# 01_stm32.net
KiCad netlist of a schematic drawn in Altium Designer
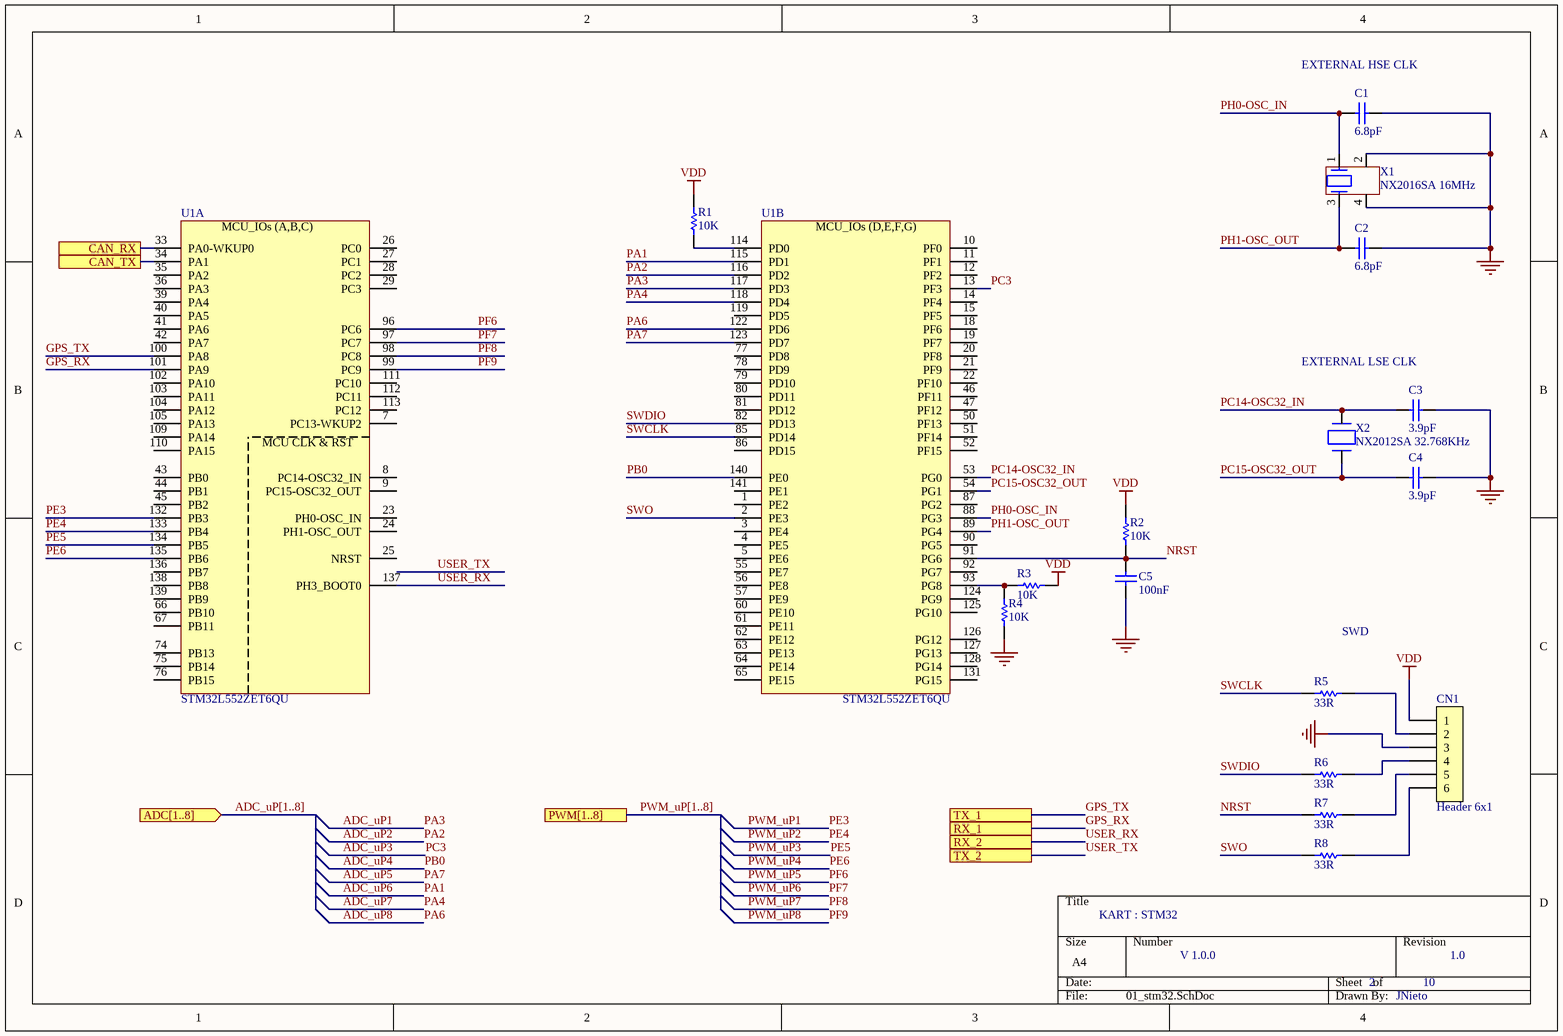
[diagram p0: 01_stm32.SchDoc]

(export (version "E")
  (design (tool "Eeschema 10.0.6"))
  (components
    (comp (ref "C1")
      (value "6.8pF")
      (footprint "C0603")
      (description "Capacitor, MLCC, 6.8pF, 50V, NPO, +-0.25pF, 0402, T=0.5mm")
      (fields
        (field (name "INTERNAL_PART_NUMBER") "MCD-00674")
        (field (name "MANUFACTURER_PART_NUMBER") "CC0402CRNPO9BN6R8")
        (field (name "PROVIDED_BY") "Subcon")
      )
      (libsource (lib "stm32l552_launchpad") (part "MCD-00674"))
    )
    (comp (ref "C2")
      (value "6.8pF")
      (footprint "C0603")
      (description "Capacitor, MLCC, 6.8pF, 50V, NPO, +-0.25pF, 0402, T=0.5mm")
      (fields
        (field (name "INTERNAL_PART_NUMBER") "MCD-00674")
        (field (name "MANUFACTURER_PART_NUMBER") "CC0402CRNPO9BN6R8")
        (field (name "PROVIDED_BY") "Subcon")
      )
      (libsource (lib "stm32l552_launchpad") (part "MCD-00674"))
    )
    (comp (ref "C3")
      (value "3.9pF")
      (footprint "C0603")
      (description "Capacitor, MLCC, 3.9pF, 50V, NPO, +-0.25pF, 0402, T=0,5mm")
      (fields
        (field (name "INTERNAL_PART_NUMBER") "MCD-00556")
        (field (name "MANUFACTURER_PART_NUMBER") "CC0402CRNPO9BN3R9")
        (field (name "PROVIDED_BY") "SUBCO")
      )
      (libsource (lib "stm32l552_launchpad") (part "MCD-00556"))
    )
    (comp (ref "C4")
      (value "3.9pF")
      (footprint "C0603")
      (description "Capacitor, MLCC, 3.9pF, 50V, NPO, +-0.25pF, 0402, T=0,5mm")
      (fields
        (field (name "INTERNAL_PART_NUMBER") "MCD-00556")
        (field (name "MANUFACTURER_PART_NUMBER") "CC0402CRNPO9BN3R9")
        (field (name "PROVIDED_BY") "SUBCO")
      )
      (libsource (lib "stm32l552_launchpad") (part "MCD-00556"))
    )
    (comp (ref "C5")
      (value "100nF")
      (footprint "C0603")
      (description "Capacitor, MLCC, 100nF, 16V, X7R, 10%, 0603, T=0,8mm")
      (fields
        (field (name "INTERNAL_PART_NUMBER") "MCD-00211")
        (field (name "MANUFACTURER_PART_NUMBER") "CC0603KRX7R7BB104")
        (field (name "PROVIDED_BY") "Subcon")
      )
      (libsource (lib "MCD_PARTS_database") (part "Capacitor"))
    )
    (comp (ref "CN1")
      (value "Header 6x1")
      (footprint "CON_SAMTEC_TSW-106-07-X-S")
      (description "Header, 6x1, 2,54mm, VR, TH, Height 5.84mm/2.54mm")
      (fields
        (field (name "INTERNAL_PART_NUMBER") "MCD-00212")
        (field (name "MANUFACTURER_PART_NUMBER") "TSW-106-07-x-S")
        (field (name "PROVIDED_BY") "Subcon")
      )
      (libsource (lib "stm32l552_launchpad") (part "MCD-00212"))
    )
    (comp (ref "R1")
      (value "10K")
      (footprint "R0603")
      (description "Resistor,10K,0603,1%,1/10W")
      (fields
        (field (name "INTERNAL_PART_NUMBER") "MCD-00220")
        (field (name "MANUFACTURER_PART_NUMBER") "RC0603FR-0710KL")
        (field (name "PROVIDED_BY") "Subcon")
      )
      (libsource (lib "MCD_PARTS_database") (part "Resistor"))
    )
    (comp (ref "R2")
      (value "10K")
      (footprint "R0603")
      (description "Resistor,10K,0603,1%,1/10W")
      (fields
        (field (name "INTERNAL_PART_NUMBER") "MCD-00220")
        (field (name "MANUFACTURER_PART_NUMBER") "RC0603FR-0710KL")
        (field (name "PROVIDED_BY") "Subcon")
      )
      (libsource (lib "MCD_PARTS_database") (part "Resistor"))
    )
    (comp (ref "R3")
      (value "10K")
      (footprint "R0603")
      (description "Resistor,10K,0603,1%,1/10W")
      (fields
        (field (name "INTERNAL_PART_NUMBER") "MCD-00220")
        (field (name "MANUFACTURER_PART_NUMBER") "RC0603FR-0710KL")
        (field (name "PROVIDED_BY") "Subcon")
      )
      (libsource (lib "MCD_PARTS_database") (part "Resistor"))
    )
    (comp (ref "R4")
      (value "10K")
      (footprint "R0603")
      (description "Resistor,10K,0603,1%,1/10W")
      (fields
        (field (name "INTERNAL_PART_NUMBER") "MCD-00220")
        (field (name "MANUFACTURER_PART_NUMBER") "RC0603FR-0710KL")
        (field (name "PROVIDED_BY") "Subcon")
      )
      (libsource (lib "MCD_PARTS_database") (part "Resistor"))
    )
    (comp (ref "R5")
      (value "33R")
      (footprint "R0603")
      (description "Resistor,33R,0603,1%,1/10W")
      (fields
        (field (name "INTERNAL_PART_NUMBER") "MCD-00190")
        (field (name "MANUFACTURER_PART_NUMBER") "RC0603FR-0722RL")
        (field (name "PROVIDED_BY") "Subcon")
      )
      (libsource (lib "stm32l552_launchpad") (part "MCD-00190"))
    )
    (comp (ref "R6")
      (value "33R")
      (footprint "R0603")
      (description "Resistor,33R,0603,1%,1/10W")
      (fields
        (field (name "INTERNAL_PART_NUMBER") "MCD-00190")
        (field (name "MANUFACTURER_PART_NUMBER") "RC0603FR-0722RL")
        (field (name "PROVIDED_BY") "Subcon")
      )
      (libsource (lib "stm32l552_launchpad") (part "MCD-00190"))
    )
    (comp (ref "R7")
      (value "33R")
      (footprint "R0603")
      (description "Resistor,33R,0603,1%,1/10W")
      (fields
        (field (name "INTERNAL_PART_NUMBER") "MCD-00190")
        (field (name "MANUFACTURER_PART_NUMBER") "RC0603FR-0722RL")
        (field (name "PROVIDED_BY") "Subcon")
      )
      (libsource (lib "stm32l552_launchpad") (part "MCD-00190"))
    )
    (comp (ref "R8")
      (value "33R")
      (footprint "R0603")
      (description "Resistor,33R,0603,1%,1/10W")
      (fields
        (field (name "INTERNAL_PART_NUMBER") "MCD-00190")
        (field (name "MANUFACTURER_PART_NUMBER") "RC0603FR-0722RL")
        (field (name "PROVIDED_BY") "Subcon")
      )
      (libsource (lib "stm32l552_launchpad") (part "MCD-00190"))
    )
    (comp (ref "U1")
      (value "STM32L552ZET6QU")
      (footprint "ICC_LQFP144_20X20_P050")
      (description "STM32L552ZET6Q MCU,LQFP144 20x20, 0.5, no AES, Q for Int SMPS")
      (fields
        (field (name "INTERNAL_PART_NUMBER") "MCD-01055")
        (field (name "MANUFACTURER") "STMICROELECTRONICS")
        (field (name "PROVIDED_BY") "SUBCO with ST control")
      )
      (libsource (lib "MCD_PARTS_database") (part "STM32L552ZET6QU"))
    )
    (comp (ref "X1")
      (value "NX2016SA 16MHz")
      (footprint "CRY_NX2016SA_4P")
      (description "Crystal 16 MHz, 8pF, -+20 PPM, R=200Ω, SMD")
      (fields
        (field (name "INTERNAL_PART_NUMBER") "MCD-01476")
        (field (name "MANUFACTURER_PART_NUMBER") "NX2016SA 16 MHz EXS00A-CS07826")
      )
      (libsource (lib "stm32l552_launchpad") (part "MCD-01476"))
    )
    (comp (ref "X2")
      (value "NX2012SA 32.768KHz")
      (footprint "CRY_NX2012SA_2P")
      (description "Crystal 32.768kHz, 6pF, -+20PPM, R=80K, SMD")
      (fields
        (field (name "INTERNAL_PART_NUMBER") "MCD-01479")
        (field (name "MANUFACTURER_PART_NUMBER") "NX2012SA 32.768KHz EXS00A-MU00527")
        (field (name "PROVIDED_BY") "SUBCO")
      )
      (libsource (lib "stm32l552_launchpad") (part "MCD-01479"))
    )
  )
  (nets
    (net (code "1") (name "/ADC_uP1") (class "Default")
      (node (ref "U1") (pin "117") (pinfunction "PD3_117") (pintype "passive"))
    )
    (net (code "2") (name "/ADC_uP2") (class "Default")
      (node (ref "U1") (pin "116") (pinfunction "PD2_116") (pintype "passive"))
    )
    (net (code "3") (name "/ADC_uP3") (class "Default")
      (node (ref "U1") (pin "13") (pinfunction "PF3_13") (pintype "passive"))
    )
    (net (code "4") (name "/ADC_uP4") (class "Default")
      (node (ref "U1") (pin "140") (pinfunction "PE0_140") (pintype "passive"))
    )
    (net (code "5") (name "/ADC_uP5") (class "Default")
      (node (ref "U1") (pin "123") (pinfunction "PD7_123") (pintype "passive"))
    )
    (net (code "6") (name "/ADC_uP6") (class "Default")
      (node (ref "U1") (pin "115") (pinfunction "PD1_115") (pintype "passive"))
    )
    (net (code "7") (name "/ADC_uP7") (class "Default")
      (node (ref "U1") (pin "118") (pinfunction "PD4_118") (pintype "passive"))
    )
    (net (code "8") (name "/ADC_uP8") (class "Default")
      (node (ref "U1") (pin "122") (pinfunction "PD6_122") (pintype "passive"))
    )
    (net (code "10") (name "/CAN_RX") (class "Default")
      (node (ref "U1") (pin "33") (pinfunction "PA0-WKUP0_33") (pintype "passive"))
    )
    (net (code "11") (name "/CAN_TX") (class "Default")
      (node (ref "U1") (pin "34") (pinfunction "PA1_34") (pintype "passive"))
    )
    (net (code "12") (name "/GPS_RX") (class "Default")
      (node (ref "U1") (pin "101") (pinfunction "PA9_101") (pintype "passive"))
    )
    (net (code "13") (name "/GPS_TX") (class "Default")
      (node (ref "U1") (pin "100") (pinfunction "PA8_100") (pintype "passive"))
    )
    (net (code "14") (name "/NRST") (class "Default")
      (node (ref "C5") (pin "2") (pinfunction "2_2") (pintype "passive"))
      (node (ref "R2") (pin "2") (pinfunction "2_2") (pintype "passive"))
      (node (ref "R7") (pin "1") (pinfunction "1_1") (pintype "passive"))
      (node (ref "U1") (pin "91") (pinfunction "PG6_91") (pintype "passive"))
    )
    (net (code "15") (name "/PC14-OSC32_IN") (class "Default")
      (node (ref "C3") (pin "1") (pinfunction "1_1") (pintype "passive"))
      (node (ref "U1") (pin "53") (pinfunction "PG0_53") (pintype "passive"))
      (node (ref "X2") (pin "2") (pinfunction "X2_2") (pintype "passive"))
    )
    (net (code "16") (name "/PC15-OSC32_OUT") (class "Default")
      (node (ref "C4") (pin "1") (pinfunction "1_1") (pintype "passive"))
      (node (ref "U1") (pin "54") (pinfunction "PG1_54") (pintype "passive"))
      (node (ref "X2") (pin "1") (pinfunction "X1_1") (pintype "passive"))
    )
    (net (code "17") (name "/PH0-OSC_IN") (class "Default")
      (node (ref "C1") (pin "1") (pinfunction "1_1") (pintype "passive"))
      (node (ref "U1") (pin "88") (pinfunction "PG3_88") (pintype "passive"))
      (node (ref "X1") (pin "1") (pinfunction "1_1") (pintype "passive"))
    )
    (net (code "18") (name "/PH1-OSC_OUT") (class "Default")
      (node (ref "C2") (pin "1") (pinfunction "1_1") (pintype "passive"))
      (node (ref "U1") (pin "89") (pinfunction "PG4_89") (pintype "passive"))
      (node (ref "X1") (pin "3") (pinfunction "3_3") (pintype "passive"))
    )
    (net (code "19") (name "/PWM_uP1") (class "Default")
      (node (ref "U1") (pin "132") (pinfunction "PB3_132") (pintype "passive"))
    )
    (net (code "20") (name "/PWM_uP2") (class "Default")
      (node (ref "U1") (pin "133") (pinfunction "PB4_133") (pintype "passive"))
    )
    (net (code "21") (name "/PWM_uP3") (class "Default")
      (node (ref "U1") (pin "134") (pinfunction "PB5_134") (pintype "passive"))
    )
    (net (code "22") (name "/PWM_uP4") (class "Default")
      (node (ref "U1") (pin "135") (pinfunction "PB6_135") (pintype "passive"))
    )
    (net (code "23") (name "/PWM_uP5") (class "Default")
      (node (ref "U1") (pin "96") (pinfunction "PC6_96") (pintype "passive"))
    )
    (net (code "24") (name "/PWM_uP6") (class "Default")
      (node (ref "U1") (pin "97") (pinfunction "PC7_97") (pintype "passive"))
    )
    (net (code "25") (name "/PWM_uP7") (class "Default")
      (node (ref "U1") (pin "98") (pinfunction "PC8_98") (pintype "passive"))
    )
    (net (code "26") (name "/PWM_uP8") (class "Default")
      (node (ref "U1") (pin "99") (pinfunction "PC9_99") (pintype "passive"))
    )
    (net (code "28") (name "/SWCLK") (class "Default")
      (node (ref "R5") (pin "1") (pinfunction "1_1") (pintype "passive"))
      (node (ref "U1") (pin "85") (pinfunction "PD14_85") (pintype "passive"))
    )
    (net (code "29") (name "/SWDIO") (class "Default")
      (node (ref "R6") (pin "1") (pinfunction "1_1") (pintype "passive"))
      (node (ref "U1") (pin "82") (pinfunction "PD13_82") (pintype "passive"))
    )
    (net (code "30") (name "/SWO") (class "Default")
      (node (ref "R8") (pin "1") (pinfunction "1_1") (pintype "passive"))
      (node (ref "U1") (pin "2") (pinfunction "PE3_2") (pintype "passive"))
    )
    (net (code "31") (name "/USER_RX") (class "Default")
      (node (ref "U1") (pin "137") (pinfunction "PH3_BOOT0_137") (pintype "passive"))
    )
    (net (code "33") (name "GND") (class "Default")
      (node (ref "C1") (pin "2") (pinfunction "2_2") (pintype "passive"))
      (node (ref "C2") (pin "2") (pinfunction "2_2") (pintype "passive"))
      (node (ref "C3") (pin "2") (pinfunction "2_2") (pintype "passive"))
      (node (ref "C4") (pin "2") (pinfunction "2_2") (pintype "passive"))
      (node (ref "C5") (pin "1") (pinfunction "1_1") (pintype "passive"))
      (node (ref "CN1") (pin "3") (pinfunction "3_3") (pintype "passive"))
      (node (ref "R4") (pin "2") (pinfunction "2_2") (pintype "passive"))
      (node (ref "X1") (pin "2") (pinfunction "2_2") (pintype "passive"))
      (node (ref "X1") (pin "4") (pinfunction "4_4") (pintype "passive"))
    )
    (net (code "34") (name "Net-(CN1-Pad2)") (class "Default")
      (node (ref "CN1") (pin "2") (pinfunction "2_2") (pintype "passive"))
      (node (ref "R5") (pin "2") (pinfunction "2_2") (pintype "passive"))
    )
    (net (code "35") (name "Net-(CN1-Pad4)") (class "Default")
      (node (ref "CN1") (pin "4") (pinfunction "4_4") (pintype "passive"))
      (node (ref "R6") (pin "2") (pinfunction "2_2") (pintype "passive"))
    )
    (net (code "36") (name "Net-(CN1-Pad5)") (class "Default")
      (node (ref "CN1") (pin "5") (pinfunction "5_5") (pintype "passive"))
      (node (ref "R7") (pin "2") (pinfunction "2_2") (pintype "passive"))
    )
    (net (code "37") (name "Net-(CN1-Pad6)") (class "Default")
      (node (ref "CN1") (pin "6") (pinfunction "6_6") (pintype "passive"))
      (node (ref "R8") (pin "2") (pinfunction "2_2") (pintype "passive"))
    )
    (net (code "38") (name "Net-(U1B-PD0)") (class "Default")
      (node (ref "R1") (pin "2") (pinfunction "2_2") (pintype "passive"))
      (node (ref "U1") (pin "114") (pinfunction "PD0_114") (pintype "passive"))
    )
    (net (code "39") (name "Net-(U1B-PG8)") (class "Default")
      (node (ref "R3") (pin "1") (pinfunction "1_1") (pintype "passive"))
      (node (ref "R4") (pin "1") (pinfunction "1_1") (pintype "passive"))
      (node (ref "U1") (pin "93") (pinfunction "PG8_93") (pintype "passive"))
    )
    (net (code "40") (name "VDD") (class "Default")
      (node (ref "CN1") (pin "1") (pinfunction "1_1") (pintype "passive"))
      (node (ref "R1") (pin "1") (pinfunction "1_1") (pintype "passive"))
      (node (ref "R2") (pin "1") (pinfunction "1_1") (pintype "passive"))
      (node (ref "R3") (pin "2") (pinfunction "2_2") (pintype "passive"))
    )
    (net (code "41") (name "unconnected-(U1A-NRST-Pad25)") (class "Default")
      (node (ref "U1") (pin "25") (pinfunction "NRST_25") (pintype "passive"))
    )
    (net (code "42") (name "unconnected-(U1A-PA2-Pad35)") (class "Default")
      (node (ref "U1") (pin "35") (pinfunction "PA2_35") (pintype "passive"))
    )
    (net (code "43") (name "unconnected-(U1A-PA3-Pad36)") (class "Default")
      (node (ref "U1") (pin "36") (pinfunction "PA3_36") (pintype "passive"))
    )
    (net (code "44") (name "unconnected-(U1A-PA4-Pad39)") (class "Default")
      (node (ref "U1") (pin "39") (pinfunction "PA4_39") (pintype "passive"))
    )
    (net (code "45") (name "unconnected-(U1A-PA5-Pad40)") (class "Default")
      (node (ref "U1") (pin "40") (pinfunction "PA5_40") (pintype "passive"))
    )
    (net (code "46") (name "unconnected-(U1A-PA6-Pad41)") (class "Default")
      (node (ref "U1") (pin "41") (pinfunction "PA6_41") (pintype "passive"))
    )
    (net (code "47") (name "unconnected-(U1A-PA7-Pad42)") (class "Default")
      (node (ref "U1") (pin "42") (pinfunction "PA7_42") (pintype "passive"))
    )
    (net (code "48") (name "unconnected-(U1A-PA10-Pad102)") (class "Default")
      (node (ref "U1") (pin "102") (pinfunction "PA10_102") (pintype "passive"))
    )
    (net (code "49") (name "unconnected-(U1A-PA11-Pad103)") (class "Default")
      (node (ref "U1") (pin "103") (pinfunction "PA11_103") (pintype "passive"))
    )
    (net (code "50") (name "unconnected-(U1A-PA12-Pad104)") (class "Default")
      (node (ref "U1") (pin "104") (pinfunction "PA12_104") (pintype "passive"))
    )
    (net (code "51") (name "unconnected-(U1A-PA13-Pad105)") (class "Default")
      (node (ref "U1") (pin "105") (pinfunction "PA13_105") (pintype "passive"))
    )
    (net (code "52") (name "unconnected-(U1A-PA14-Pad109)") (class "Default")
      (node (ref "U1") (pin "109") (pinfunction "PA14_109") (pintype "passive"))
    )
    (net (code "53") (name "unconnected-(U1A-PA15-Pad110)") (class "Default")
      (node (ref "U1") (pin "110") (pinfunction "PA15_110") (pintype "passive"))
    )
    (net (code "54") (name "unconnected-(U1A-PB0-Pad43)") (class "Default")
      (node (ref "U1") (pin "43") (pinfunction "PB0_43") (pintype "passive"))
    )
    (net (code "55") (name "unconnected-(U1A-PB1-Pad44)") (class "Default")
      (node (ref "U1") (pin "44") (pinfunction "PB1_44") (pintype "passive"))
    )
    (net (code "56") (name "unconnected-(U1A-PB2-Pad45)") (class "Default")
      (node (ref "U1") (pin "45") (pinfunction "PB2_45") (pintype "passive"))
    )
    (net (code "57") (name "unconnected-(U1A-PB7-Pad136)") (class "Default")
      (node (ref "U1") (pin "136") (pinfunction "PB7_136") (pintype "passive"))
    )
    (net (code "58") (name "unconnected-(U1A-PB8-Pad138)") (class "Default")
      (node (ref "U1") (pin "138") (pinfunction "PB8_138") (pintype "passive"))
    )
    (net (code "59") (name "unconnected-(U1A-PB9-Pad139)") (class "Default")
      (node (ref "U1") (pin "139") (pinfunction "PB9_139") (pintype "passive"))
    )
    (net (code "60") (name "unconnected-(U1A-PB10-Pad66)") (class "Default")
      (node (ref "U1") (pin "66") (pinfunction "PB10_66") (pintype "passive"))
    )
    (net (code "61") (name "unconnected-(U1A-PB11-Pad67)") (class "Default")
      (node (ref "U1") (pin "67") (pinfunction "PB11_67") (pintype "passive"))
    )
    (net (code "62") (name "unconnected-(U1A-PB13-Pad74)") (class "Default")
      (node (ref "U1") (pin "74") (pinfunction "PB13_74") (pintype "passive"))
    )
    (net (code "63") (name "unconnected-(U1A-PB14-Pad75)") (class "Default")
      (node (ref "U1") (pin "75") (pinfunction "PB14_75") (pintype "passive"))
    )
    (net (code "64") (name "unconnected-(U1A-PB15-Pad76)") (class "Default")
      (node (ref "U1") (pin "76") (pinfunction "PB15_76") (pintype "passive"))
    )
    (net (code "65") (name "unconnected-(U1A-PC0-Pad26)") (class "Default")
      (node (ref "U1") (pin "26") (pinfunction "PC0_26") (pintype "passive"))
    )
    (net (code "66") (name "unconnected-(U1A-PC1-Pad27)") (class "Default")
      (node (ref "U1") (pin "27") (pinfunction "PC1_27") (pintype "passive"))
    )
    (net (code "67") (name "unconnected-(U1A-PC2-Pad28)") (class "Default")
      (node (ref "U1") (pin "28") (pinfunction "PC2_28") (pintype "passive"))
    )
    (net (code "68") (name "unconnected-(U1A-PC3-Pad29)") (class "Default")
      (node (ref "U1") (pin "29") (pinfunction "PC3_29") (pintype "passive"))
    )
    (net (code "69") (name "unconnected-(U1A-PC10-Pad111)") (class "Default")
      (node (ref "U1") (pin "111") (pinfunction "PC10_111") (pintype "passive"))
    )
    (net (code "70") (name "unconnected-(U1A-PC11-Pad112)") (class "Default")
      (node (ref "U1") (pin "112") (pinfunction "PC11_112") (pintype "passive"))
    )
    (net (code "71") (name "unconnected-(U1A-PC12-Pad113)") (class "Default")
      (node (ref "U1") (pin "113") (pinfunction "PC12_113") (pintype "passive"))
    )
    (net (code "72") (name "unconnected-(U1A-PC13-WKUP2-Pad7)") (class "Default")
      (node (ref "U1") (pin "7") (pinfunction "PC13-WKUP2_7") (pintype "passive"))
    )
    (net (code "73") (name "unconnected-(U1A-PC14-OSC32_IN-Pad8)") (class "Default")
      (node (ref "U1") (pin "8") (pinfunction "PC14-OSC32_IN_8") (pintype "passive"))
    )
    (net (code "74") (name "unconnected-(U1A-PC15-OSC32_OUT-Pad9)") (class "Default")
      (node (ref "U1") (pin "9") (pinfunction "PC15-OSC32_OUT_9") (pintype "passive"))
    )
    (net (code "75") (name "unconnected-(U1A-PH0-OSC_IN-Pad23)") (class "Default")
      (node (ref "U1") (pin "23") (pinfunction "PH0-OSC_IN_23") (pintype "passive"))
    )
    (net (code "76") (name "unconnected-(U1A-PH1-OSC_OUT-Pad24)") (class "Default")
      (node (ref "U1") (pin "24") (pinfunction "PH1-OSC_OUT_24") (pintype "passive"))
    )
    (net (code "77") (name "unconnected-(U1B-PD5-Pad119)") (class "Default")
      (node (ref "U1") (pin "119") (pinfunction "PD5_119") (pintype "passive"))
    )
    (net (code "78") (name "unconnected-(U1B-PD8-Pad77)") (class "Default")
      (node (ref "U1") (pin "77") (pinfunction "PD8_77") (pintype "passive"))
    )
    (net (code "79") (name "unconnected-(U1B-PD9-Pad78)") (class "Default")
      (node (ref "U1") (pin "78") (pinfunction "PD9_78") (pintype "passive"))
    )
    (net (code "80") (name "unconnected-(U1B-PD10-Pad79)") (class "Default")
      (node (ref "U1") (pin "79") (pinfunction "PD10_79") (pintype "passive"))
    )
    (net (code "81") (name "unconnected-(U1B-PD11-Pad80)") (class "Default")
      (node (ref "U1") (pin "80") (pinfunction "PD11_80") (pintype "passive"))
    )
    (net (code "82") (name "unconnected-(U1B-PD12-Pad81)") (class "Default")
      (node (ref "U1") (pin "81") (pinfunction "PD12_81") (pintype "passive"))
    )
    (net (code "83") (name "unconnected-(U1B-PD15-Pad86)") (class "Default")
      (node (ref "U1") (pin "86") (pinfunction "PD15_86") (pintype "passive"))
    )
    (net (code "84") (name "unconnected-(U1B-PE1-Pad141)") (class "Default")
      (node (ref "U1") (pin "141") (pinfunction "PE1_141") (pintype "passive"))
    )
    (net (code "85") (name "unconnected-(U1B-PE2-Pad1)") (class "Default")
      (node (ref "U1") (pin "1") (pinfunction "PE2_1") (pintype "passive"))
    )
    (net (code "86") (name "unconnected-(U1B-PE4-Pad3)") (class "Default")
      (node (ref "U1") (pin "3") (pinfunction "PE4_3") (pintype "passive"))
    )
    (net (code "87") (name "unconnected-(U1B-PE5-Pad4)") (class "Default")
      (node (ref "U1") (pin "4") (pinfunction "PE5_4") (pintype "passive"))
    )
    (net (code "88") (name "unconnected-(U1B-PE6-Pad5)") (class "Default")
      (node (ref "U1") (pin "5") (pinfunction "PE6_5") (pintype "passive"))
    )
    (net (code "89") (name "unconnected-(U1B-PE7-Pad55)") (class "Default")
      (node (ref "U1") (pin "55") (pinfunction "PE7_55") (pintype "passive"))
    )
    (net (code "90") (name "unconnected-(U1B-PE8-Pad56)") (class "Default")
      (node (ref "U1") (pin "56") (pinfunction "PE8_56") (pintype "passive"))
    )
    (net (code "91") (name "unconnected-(U1B-PE9-Pad57)") (class "Default")
      (node (ref "U1") (pin "57") (pinfunction "PE9_57") (pintype "passive"))
    )
    (net (code "92") (name "unconnected-(U1B-PE10-Pad60)") (class "Default")
      (node (ref "U1") (pin "60") (pinfunction "PE10_60") (pintype "passive"))
    )
    (net (code "93") (name "unconnected-(U1B-PE11-Pad61)") (class "Default")
      (node (ref "U1") (pin "61") (pinfunction "PE11_61") (pintype "passive"))
    )
    (net (code "94") (name "unconnected-(U1B-PE12-Pad62)") (class "Default")
      (node (ref "U1") (pin "62") (pinfunction "PE12_62") (pintype "passive"))
    )
    (net (code "95") (name "unconnected-(U1B-PE13-Pad63)") (class "Default")
      (node (ref "U1") (pin "63") (pinfunction "PE13_63") (pintype "passive"))
    )
    (net (code "96") (name "unconnected-(U1B-PE14-Pad64)") (class "Default")
      (node (ref "U1") (pin "64") (pinfunction "PE14_64") (pintype "passive"))
    )
    (net (code "97") (name "unconnected-(U1B-PE15-Pad65)") (class "Default")
      (node (ref "U1") (pin "65") (pinfunction "PE15_65") (pintype "passive"))
    )
    (net (code "98") (name "unconnected-(U1B-PF0-Pad10)") (class "Default")
      (node (ref "U1") (pin "10") (pinfunction "PF0_10") (pintype "passive"))
    )
    (net (code "99") (name "unconnected-(U1B-PF1-Pad11)") (class "Default")
      (node (ref "U1") (pin "11") (pinfunction "PF1_11") (pintype "passive"))
    )
    (net (code "100") (name "unconnected-(U1B-PF2-Pad12)") (class "Default")
      (node (ref "U1") (pin "12") (pinfunction "PF2_12") (pintype "passive"))
    )
    (net (code "101") (name "unconnected-(U1B-PF4-Pad14)") (class "Default")
      (node (ref "U1") (pin "14") (pinfunction "PF4_14") (pintype "passive"))
    )
    (net (code "102") (name "unconnected-(U1B-PF5-Pad15)") (class "Default")
      (node (ref "U1") (pin "15") (pinfunction "PF5_15") (pintype "passive"))
    )
    (net (code "103") (name "unconnected-(U1B-PF6-Pad18)") (class "Default")
      (node (ref "U1") (pin "18") (pinfunction "PF6_18") (pintype "passive"))
    )
    (net (code "104") (name "unconnected-(U1B-PF7-Pad19)") (class "Default")
      (node (ref "U1") (pin "19") (pinfunction "PF7_19") (pintype "passive"))
    )
    (net (code "105") (name "unconnected-(U1B-PF8-Pad20)") (class "Default")
      (node (ref "U1") (pin "20") (pinfunction "PF8_20") (pintype "passive"))
    )
    (net (code "106") (name "unconnected-(U1B-PF9-Pad21)") (class "Default")
      (node (ref "U1") (pin "21") (pinfunction "PF9_21") (pintype "passive"))
    )
    (net (code "107") (name "unconnected-(U1B-PF10-Pad22)") (class "Default")
      (node (ref "U1") (pin "22") (pinfunction "PF10_22") (pintype "passive"))
    )
    (net (code "108") (name "unconnected-(U1B-PF11-Pad46)") (class "Default")
      (node (ref "U1") (pin "46") (pinfunction "PF11_46") (pintype "passive"))
    )
    (net (code "109") (name "unconnected-(U1B-PF12-Pad47)") (class "Default")
      (node (ref "U1") (pin "47") (pinfunction "PF12_47") (pintype "passive"))
    )
    (net (code "110") (name "unconnected-(U1B-PF13-Pad50)") (class "Default")
      (node (ref "U1") (pin "50") (pinfunction "PF13_50") (pintype "passive"))
    )
    (net (code "111") (name "unconnected-(U1B-PF14-Pad51)") (class "Default")
      (node (ref "U1") (pin "51") (pinfunction "PF14_51") (pintype "passive"))
    )
    (net (code "112") (name "unconnected-(U1B-PF15-Pad52)") (class "Default")
      (node (ref "U1") (pin "52") (pinfunction "PF15_52") (pintype "passive"))
    )
    (net (code "113") (name "unconnected-(U1B-PG2-Pad87)") (class "Default")
      (node (ref "U1") (pin "87") (pinfunction "PG2_87") (pintype "passive"))
    )
    (net (code "114") (name "unconnected-(U1B-PG5-Pad90)") (class "Default")
      (node (ref "U1") (pin "90") (pinfunction "PG5_90") (pintype "passive"))
    )
    (net (code "115") (name "unconnected-(U1B-PG7-Pad92)") (class "Default")
      (node (ref "U1") (pin "92") (pinfunction "PG7_92") (pintype "passive"))
    )
    (net (code "116") (name "unconnected-(U1B-PG9-Pad124)") (class "Default")
      (node (ref "U1") (pin "124") (pinfunction "PG9_124") (pintype "passive"))
    )
    (net (code "117") (name "unconnected-(U1B-PG10-Pad125)") (class "Default")
      (node (ref "U1") (pin "125") (pinfunction "PG10_125") (pintype "passive"))
    )
    (net (code "118") (name "unconnected-(U1B-PG12-Pad126)") (class "Default")
      (node (ref "U1") (pin "126") (pinfunction "PG12_126") (pintype "passive"))
    )
    (net (code "119") (name "unconnected-(U1B-PG13-Pad127)") (class "Default")
      (node (ref "U1") (pin "127") (pinfunction "PG13_127") (pintype "passive"))
    )
    (net (code "120") (name "unconnected-(U1B-PG14-Pad128)") (class "Default")
      (node (ref "U1") (pin "128") (pinfunction "PG14_128") (pintype "passive"))
    )
    (net (code "121") (name "unconnected-(U1B-PG15-Pad131)") (class "Default")
      (node (ref "U1") (pin "131") (pinfunction "PG15_131") (pintype "passive"))
    )
  )
)
